# ESP07.net
KiCad netlist of a schematic drawn in Altium Designer
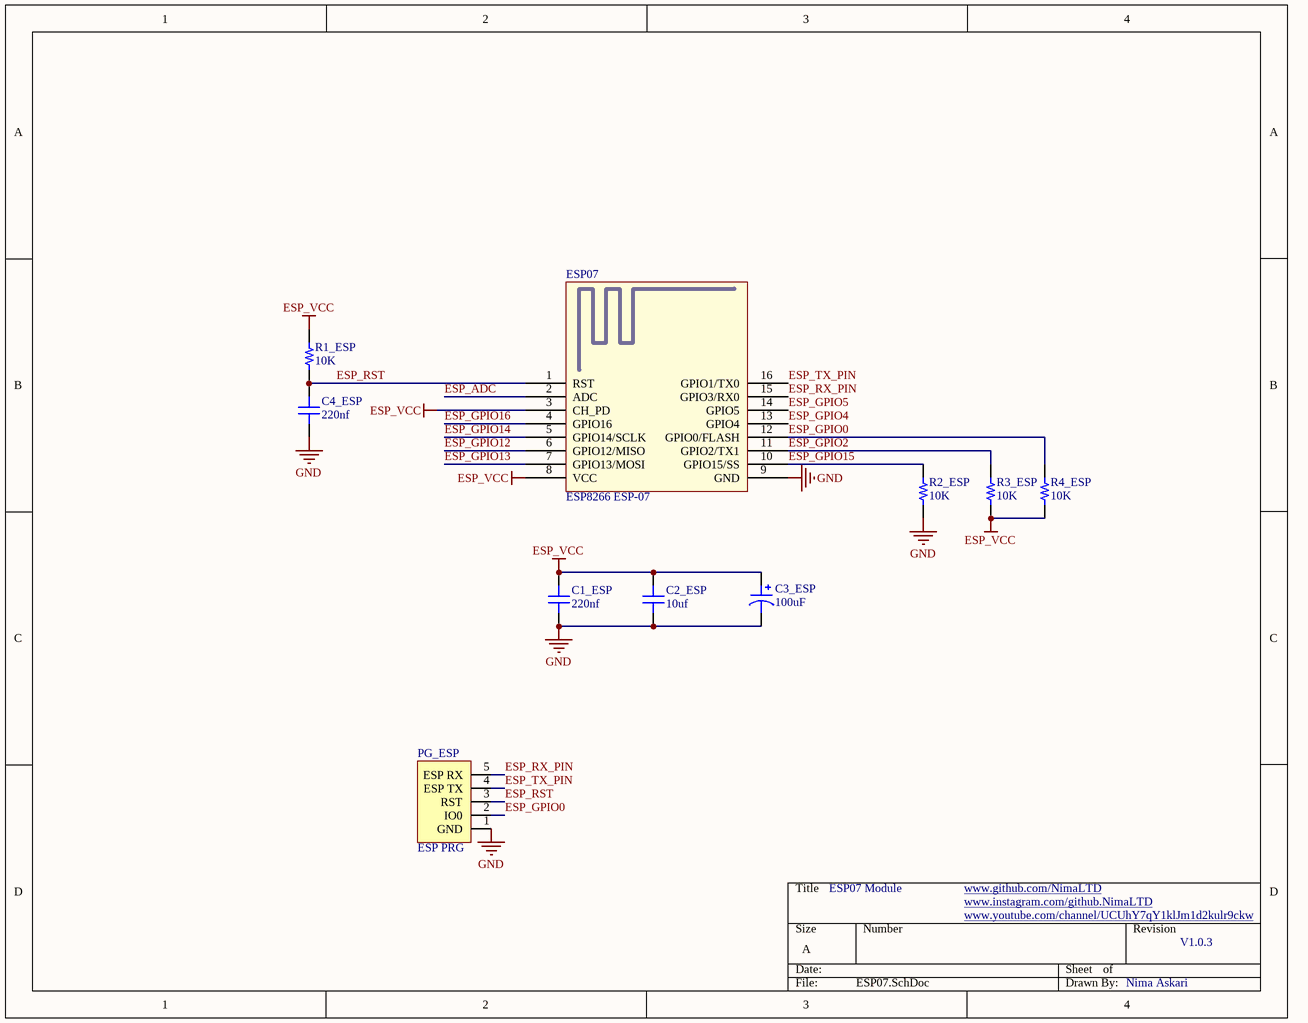
[diagram p0: ESP07.SchDoc]

(export (version "E")
  (design (tool "Eeschema 10.0.6"))
  (components
    (comp (ref "C1_ESP")
      (value "220nf")
      (footprint "CAP 0805")
      (description "SMT Capacitor")
      (libsource (lib "CAPACITOR") (part "Cap SMD 0805"))
    )
    (comp (ref "C2_ESP")
      (value "10uf")
      (footprint "CAP 0805")
      (description "SMT Capacitor")
      (libsource (lib "CAPACITOR") (part "Cap SMD 0805"))
    )
    (comp (ref "C3_ESP")
      (value "100uF")
      (footprint "CAP AL SMD D6 H6")
      (description "SMT Polarised Capacitor")
      (libsource (lib "CAPACITOR") (part "Pol Cap SMD AL D6 H6"))
    )
    (comp (ref "C4_ESP")
      (value "220nf")
      (footprint "CAP 0805")
      (description "SMT Capacitor")
      (libsource (lib "CAPACITOR") (part "Cap SMD 0805"))
    )
    (comp (ref "ESP07")
      (value "ESP8266 ESP-07")
      (footprint "M_ESP07")
      (libsource (lib "MODULE") (part "ESP8266 ESP-07"))
    )
    (comp (ref "PG_ESP")
      (value "ESP PRG")
      (footprint "HDR2_M_1X5")
      (libsource (lib "CONNECTOR") (part "ESP PRG P2.0"))
    )
    (comp (ref "R1_ESP")
      (value "10K")
      (footprint "RES 0805")
      (description "SMD Resistor")
      (libsource (lib "RESISTOR") (part "Res SMD 0805"))
    )
    (comp (ref "R2_ESP")
      (value "10K")
      (footprint "RES 0805")
      (description "SMD Resistor")
      (libsource (lib "RESISTOR") (part "Res SMD 0805"))
    )
    (comp (ref "R3_ESP")
      (value "10K")
      (footprint "RES 0805")
      (description "SMD Resistor")
      (libsource (lib "RESISTOR") (part "Res SMD 0805"))
    )
    (comp (ref "R4_ESP")
      (value "10K")
      (footprint "RES 0805")
      (description "SMD Resistor")
      (libsource (lib "RESISTOR") (part "Res SMD 0805"))
    )
  )
  (nets
    (net (code "1") (name "/ESP_ADC") (class "Default")
      (node (ref "ESP07") (pin "2") (pinfunction "ADC_2") (pintype "passive"))
    )
    (net (code "2") (name "/ESP_GPIO0") (class "Default")
      (node (ref "ESP07") (pin "12") (pinfunction "GPIO0/FLASH_12") (pintype "passive"))
      (node (ref "PG_ESP") (pin "2") (pinfunction "IO0_2") (pintype "passive"))
      (node (ref "R4_ESP") (pin "1") (pinfunction "1_1") (pintype "passive"))
    )
    (net (code "3") (name "/ESP_GPIO2") (class "Default")
      (node (ref "ESP07") (pin "11") (pinfunction "GPIO2/TX1_11") (pintype "passive"))
      (node (ref "R3_ESP") (pin "1") (pinfunction "1_1") (pintype "passive"))
    )
    (net (code "4") (name "/ESP_GPIO4") (class "Default")
      (node (ref "ESP07") (pin "13") (pinfunction "GPIO4_13") (pintype "passive"))
    )
    (net (code "5") (name "/ESP_GPIO5") (class "Default")
      (node (ref "ESP07") (pin "14") (pinfunction "GPIO5_14") (pintype "passive"))
    )
    (net (code "6") (name "/ESP_GPIO12") (class "Default")
      (node (ref "ESP07") (pin "6") (pinfunction "GPIO12/MISO_6") (pintype "passive"))
    )
    (net (code "7") (name "/ESP_GPIO13") (class "Default")
      (node (ref "ESP07") (pin "7") (pinfunction "GPIO13/MOSI_7") (pintype "passive"))
    )
    (net (code "8") (name "/ESP_GPIO14") (class "Default")
      (node (ref "ESP07") (pin "5") (pinfunction "GPIO14/SCLK_5") (pintype "passive"))
    )
    (net (code "9") (name "/ESP_GPIO15") (class "Default")
      (node (ref "ESP07") (pin "10") (pinfunction "GPIO15/SS_10") (pintype "passive"))
      (node (ref "R2_ESP") (pin "1") (pinfunction "1_1") (pintype "passive"))
    )
    (net (code "10") (name "/ESP_GPIO16") (class "Default")
      (node (ref "ESP07") (pin "4") (pinfunction "GPIO16_4") (pintype "passive"))
    )
    (net (code "11") (name "/ESP_RST") (class "Default")
      (node (ref "C4_ESP") (pin "2") (pinfunction "2_2") (pintype "passive"))
      (node (ref "ESP07") (pin "1") (pinfunction "RST_1") (pintype "power_in"))
      (node (ref "PG_ESP") (pin "3") (pinfunction "RST_3") (pintype "passive"))
      (node (ref "R1_ESP") (pin "1") (pinfunction "1_1") (pintype "passive"))
    )
    (net (code "12") (name "/ESP_RX_PIN") (class "Default")
      (node (ref "ESP07") (pin "15") (pinfunction "GPIO3/RX0_15") (pintype "passive"))
      (node (ref "PG_ESP") (pin "5") (pinfunction "ESP_RX_5") (pintype "passive"))
    )
    (net (code "13") (name "/ESP_TX_PIN") (class "Default")
      (node (ref "ESP07") (pin "16") (pinfunction "GPIO1/TX0_16") (pintype "passive"))
      (node (ref "PG_ESP") (pin "4") (pinfunction "ESP_TX_4") (pintype "passive"))
    )
    (net (code "14") (name "ESP_VCC") (class "Default")
      (node (ref "C1_ESP") (pin "2") (pinfunction "2_2") (pintype "passive"))
      (node (ref "C2_ESP") (pin "2") (pinfunction "2_2") (pintype "passive"))
      (node (ref "C3_ESP") (pin "1") (pinfunction "1_1") (pintype "passive"))
      (node (ref "ESP07") (pin "3") (pinfunction "CH_PD_3") (pintype "passive"))
      (node (ref "ESP07") (pin "8") (pinfunction "VCC_8") (pintype "passive"))
      (node (ref "R1_ESP") (pin "2") (pinfunction "2_2") (pintype "passive"))
      (node (ref "R3_ESP") (pin "2") (pinfunction "2_2") (pintype "passive"))
      (node (ref "R4_ESP") (pin "2") (pinfunction "2_2") (pintype "passive"))
    )
    (net (code "15") (name "GND") (class "Default")
      (node (ref "C1_ESP") (pin "1") (pinfunction "1_1") (pintype "passive"))
      (node (ref "C2_ESP") (pin "1") (pinfunction "1_1") (pintype "passive"))
      (node (ref "C3_ESP") (pin "2") (pinfunction "2_2") (pintype "passive"))
      (node (ref "C4_ESP") (pin "1") (pinfunction "1_1") (pintype "passive"))
      (node (ref "ESP07") (pin "9") (pinfunction "GND_9") (pintype "passive"))
      (node (ref "PG_ESP") (pin "1") (pinfunction "GND_1") (pintype "passive"))
      (node (ref "R2_ESP") (pin "2") (pinfunction "2_2") (pintype "passive"))
    )
  )
)
